# flight_unit.net
KiCad netlist of a schematic drawn in EAGLE
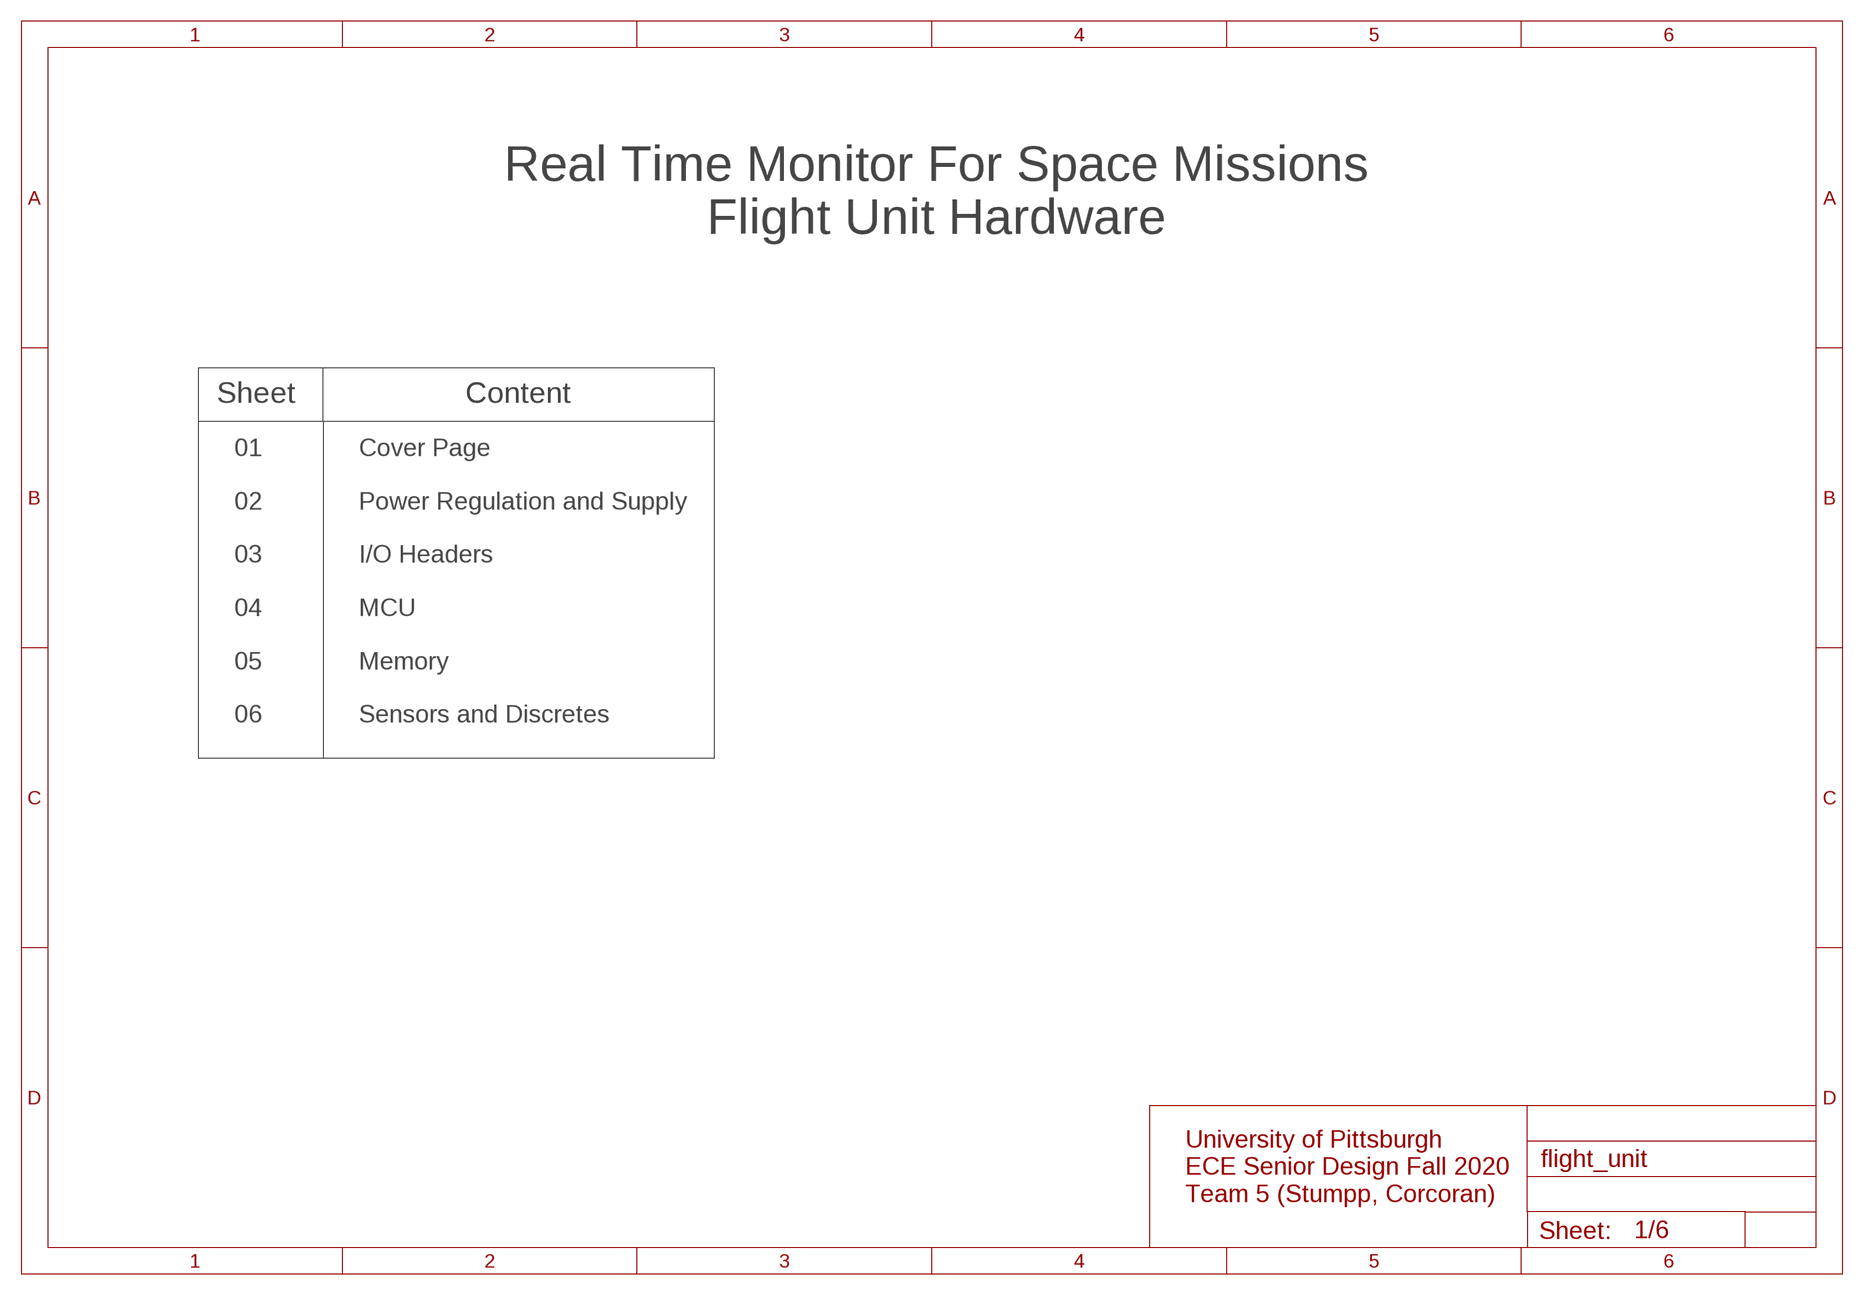
[diagram p0: schematic, sheet 1]
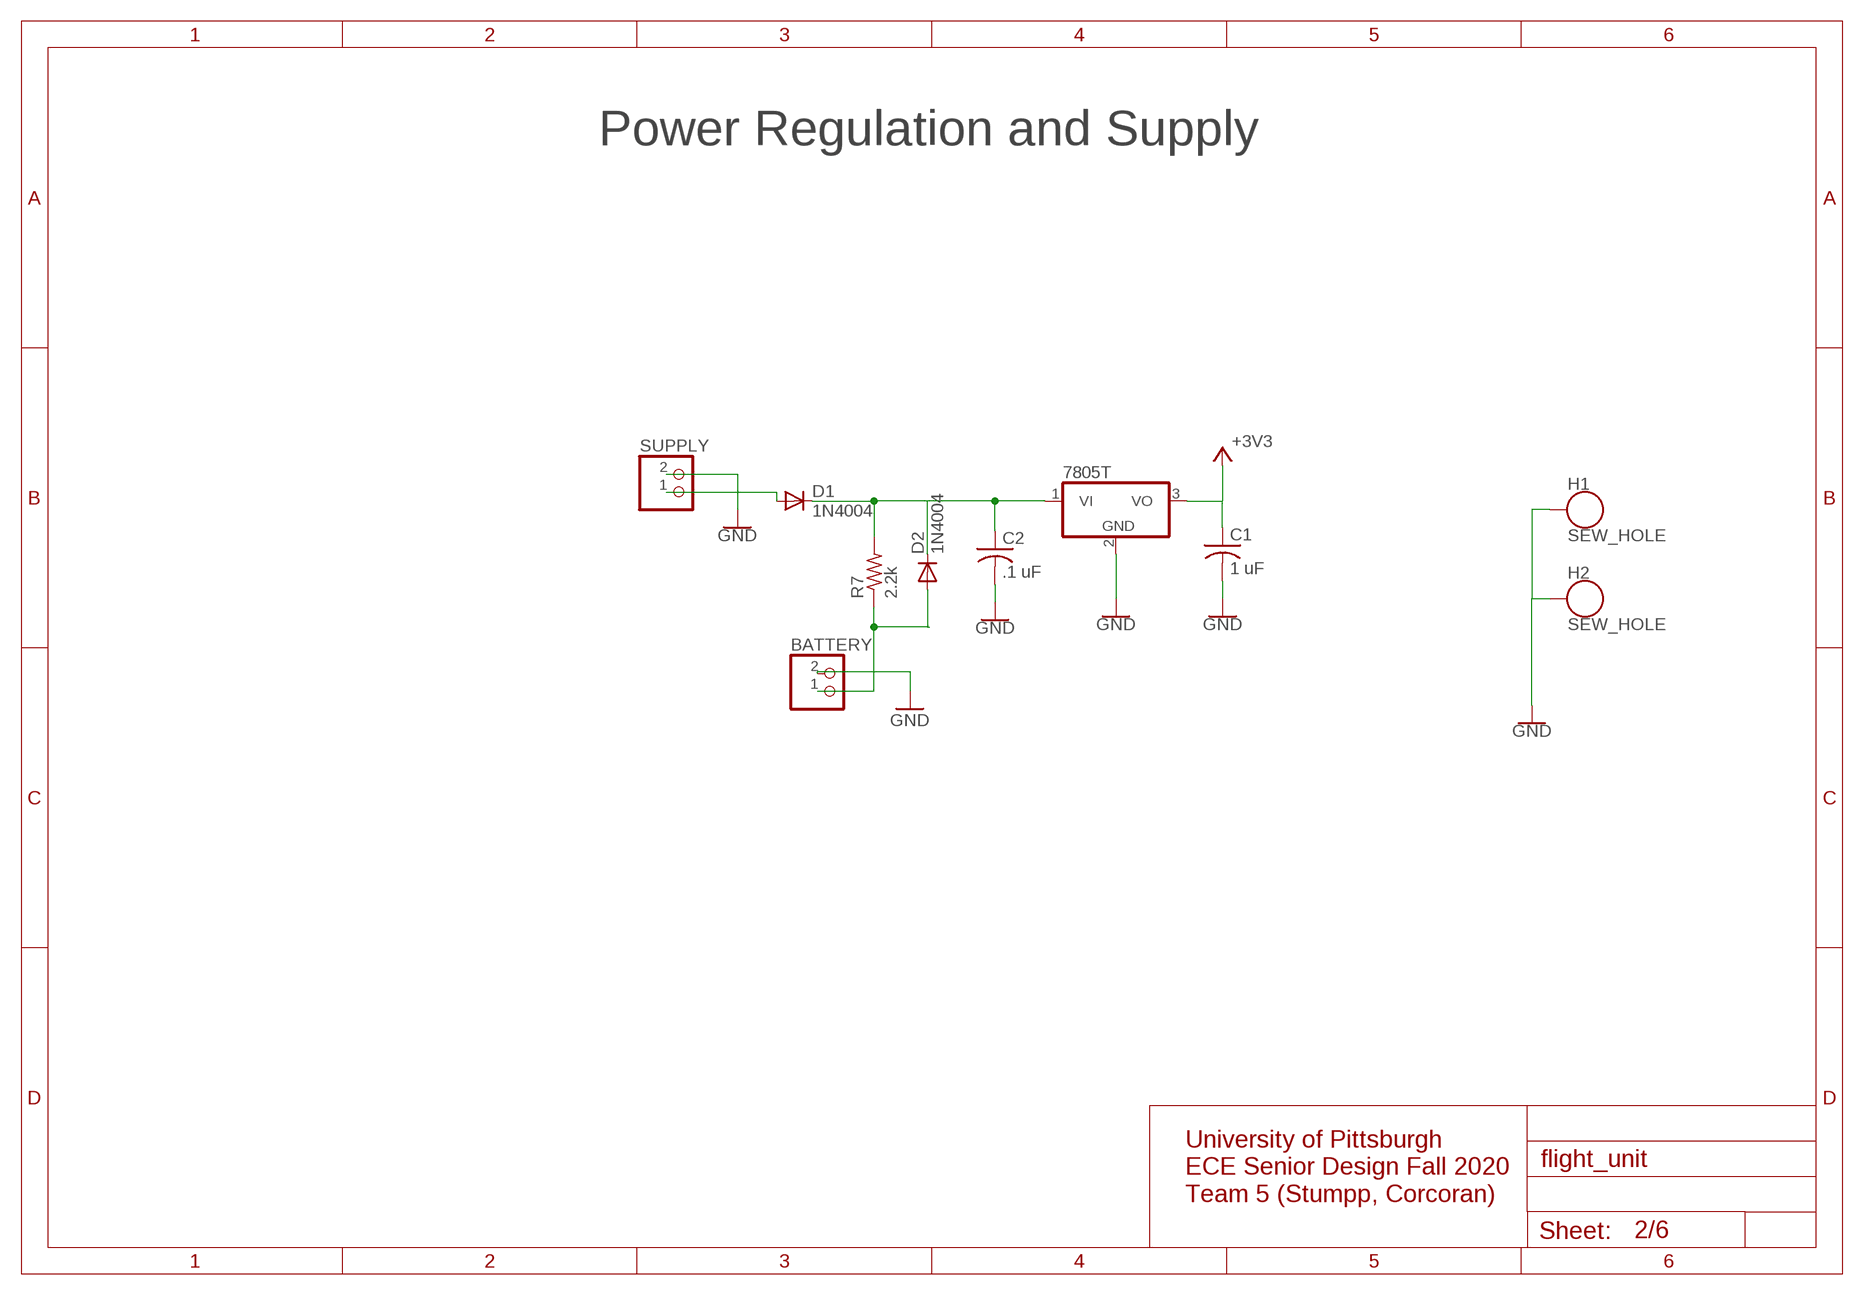
[diagram p1: schematic, sheet 2]
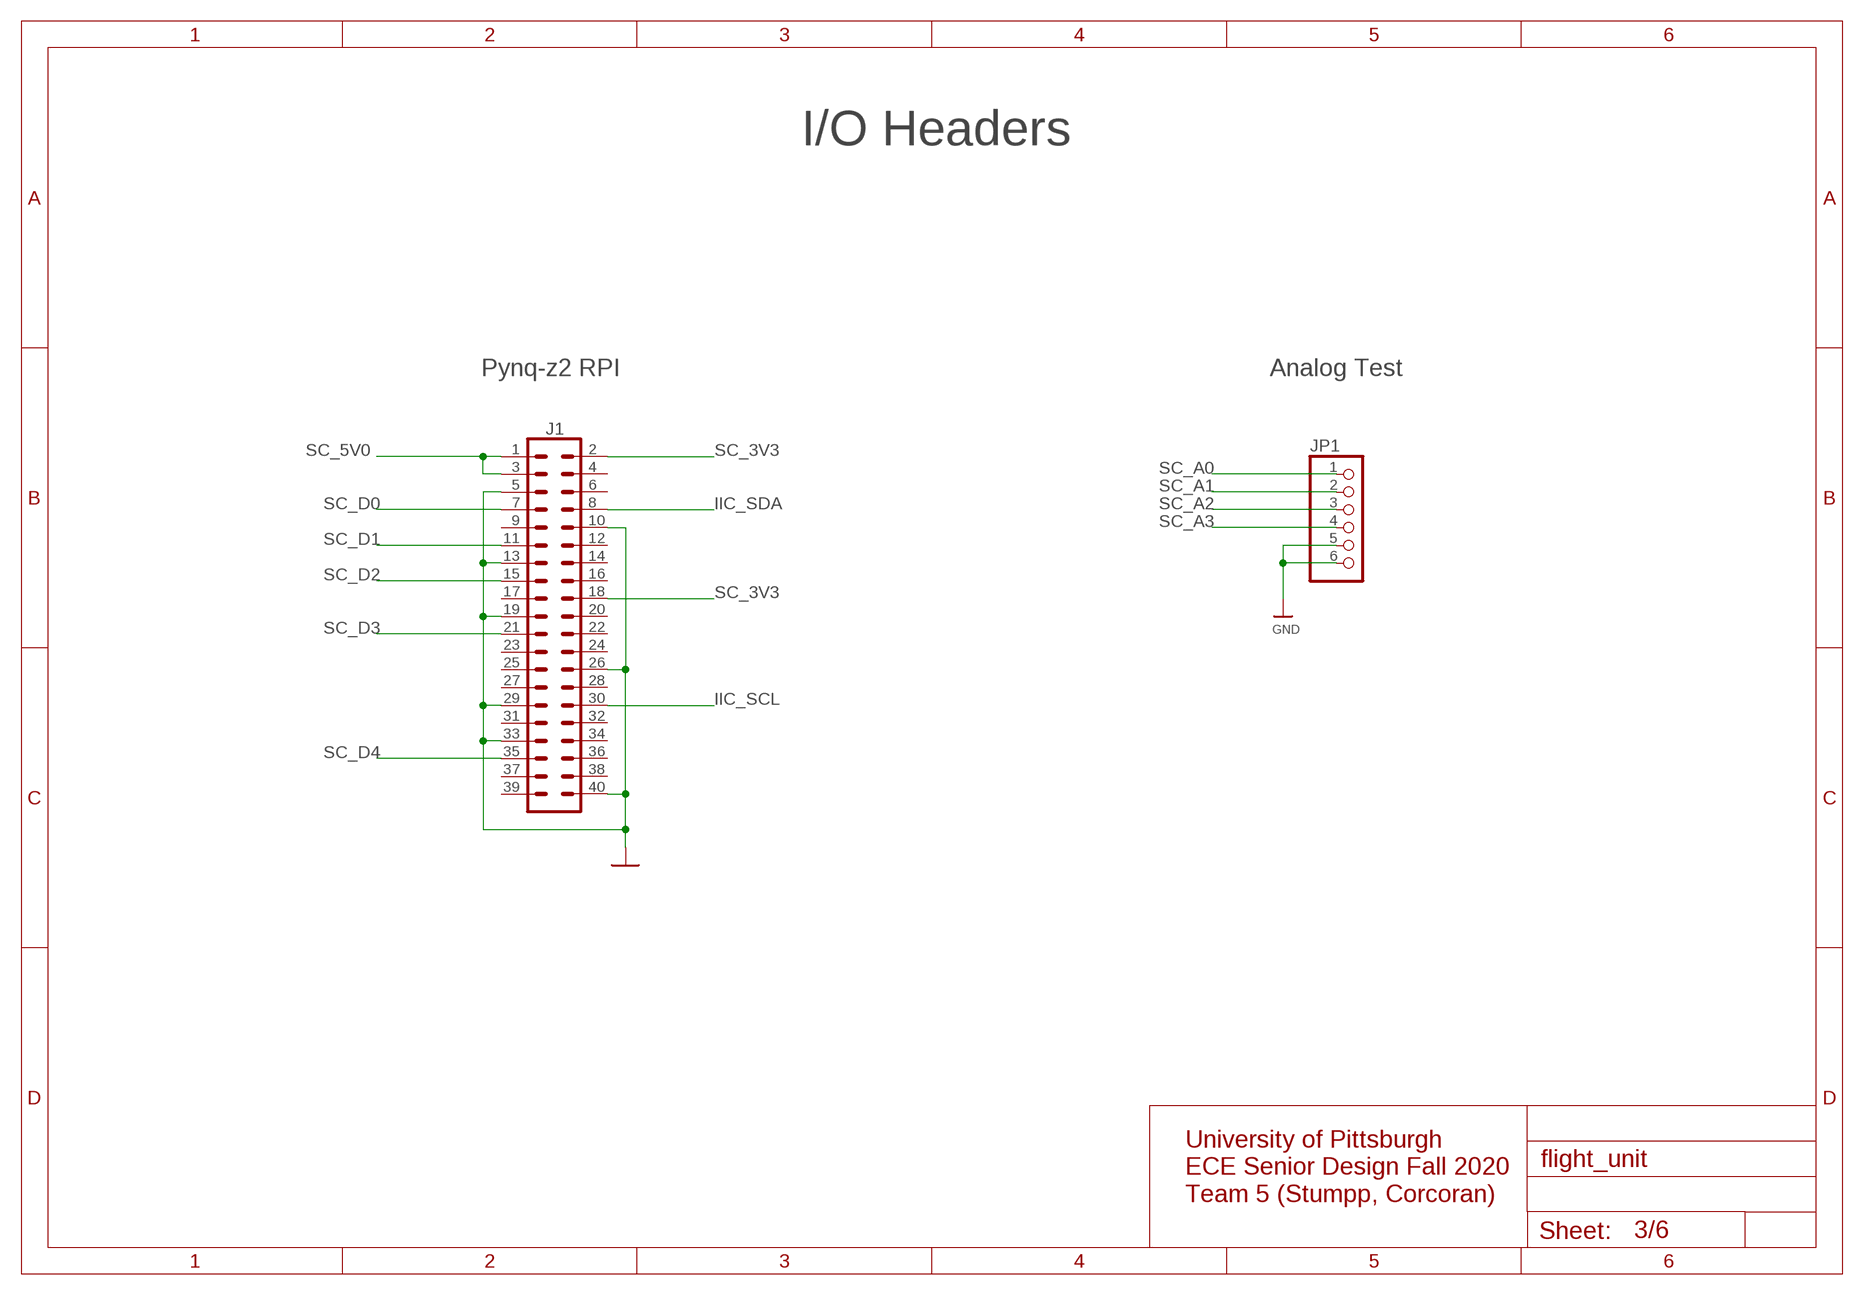
[diagram p2: schematic, sheet 3]
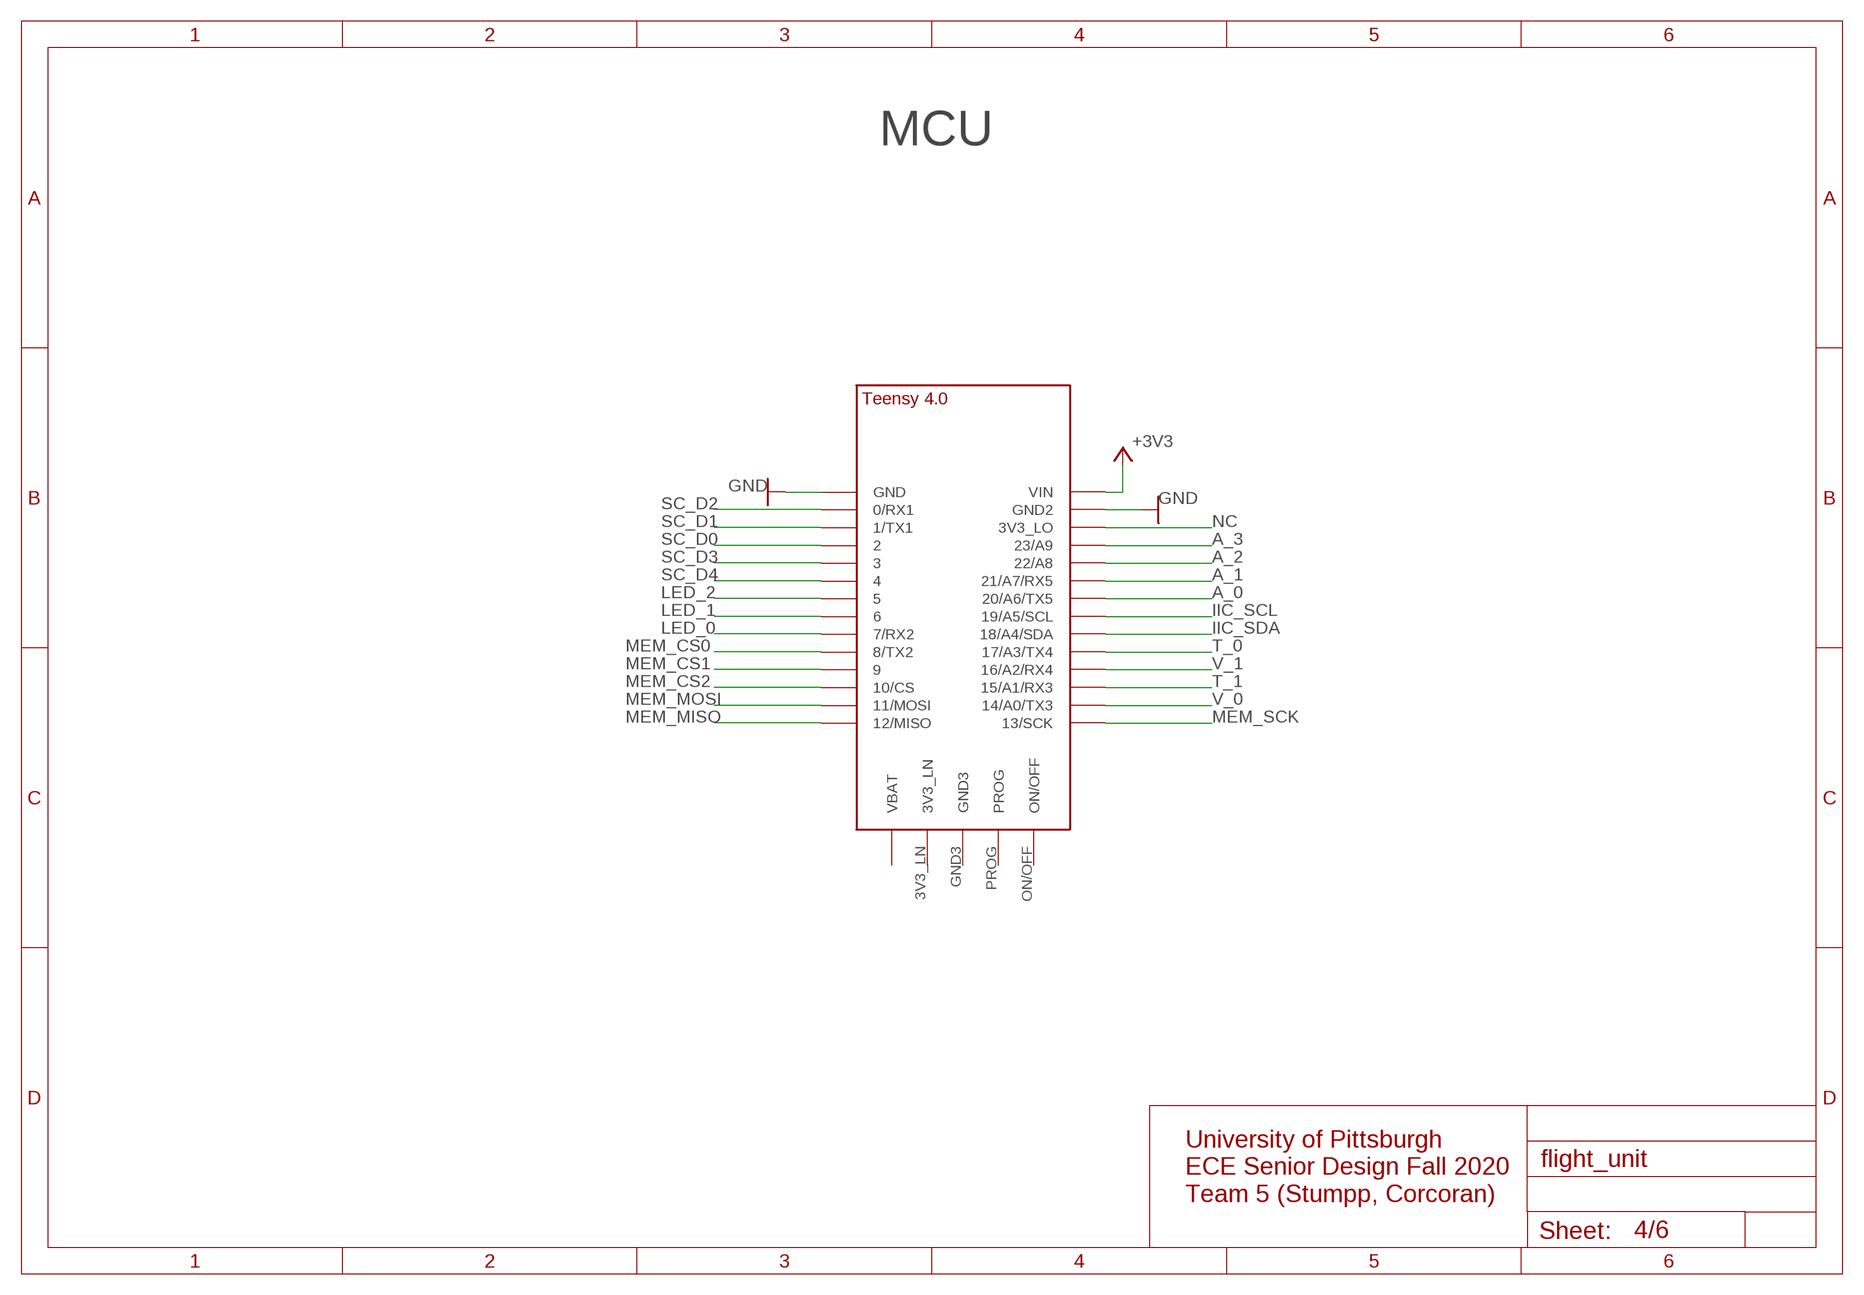
[diagram p3: schematic, sheet 4]
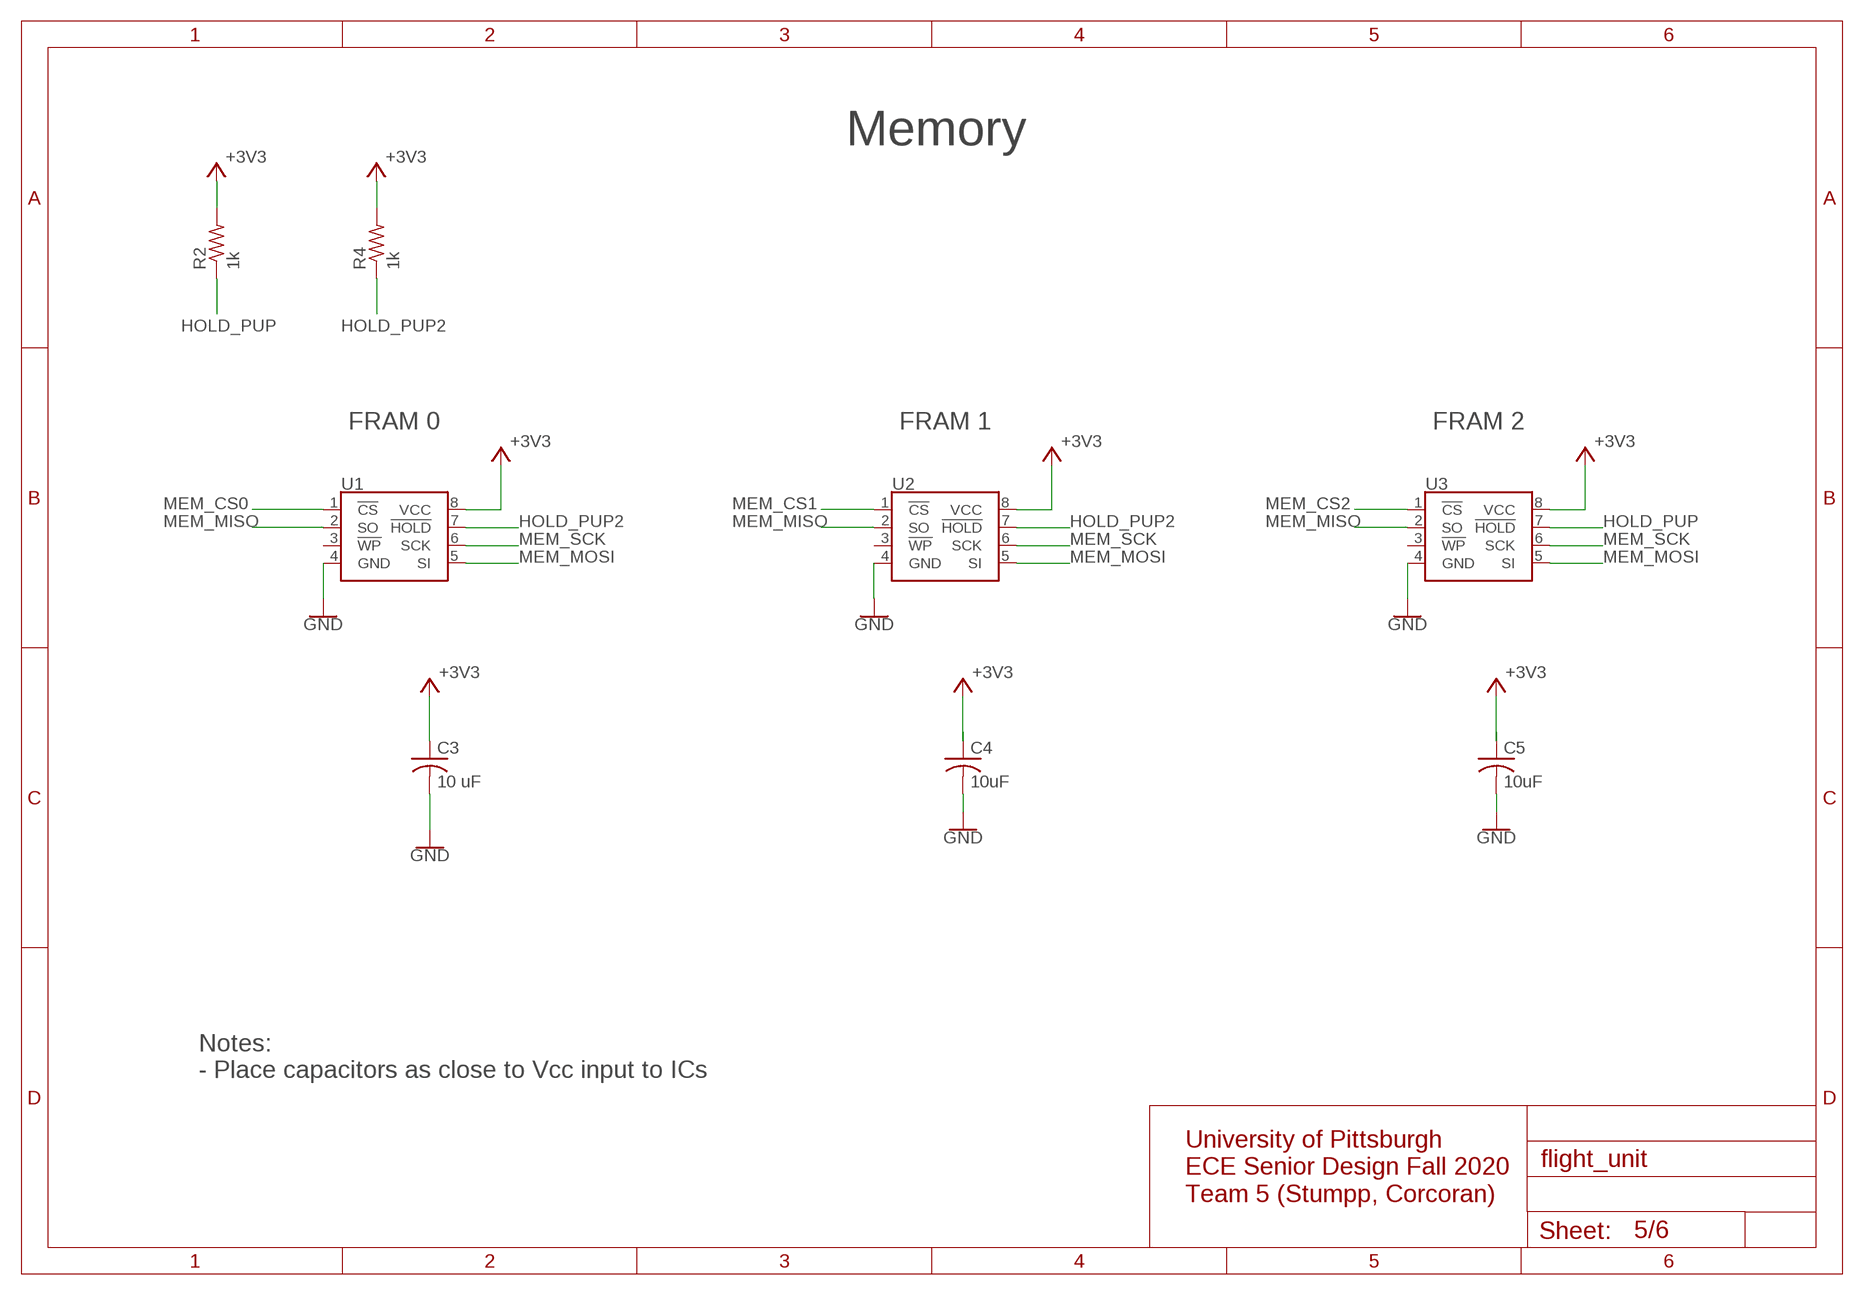
[diagram p4: schematic, sheet 5]
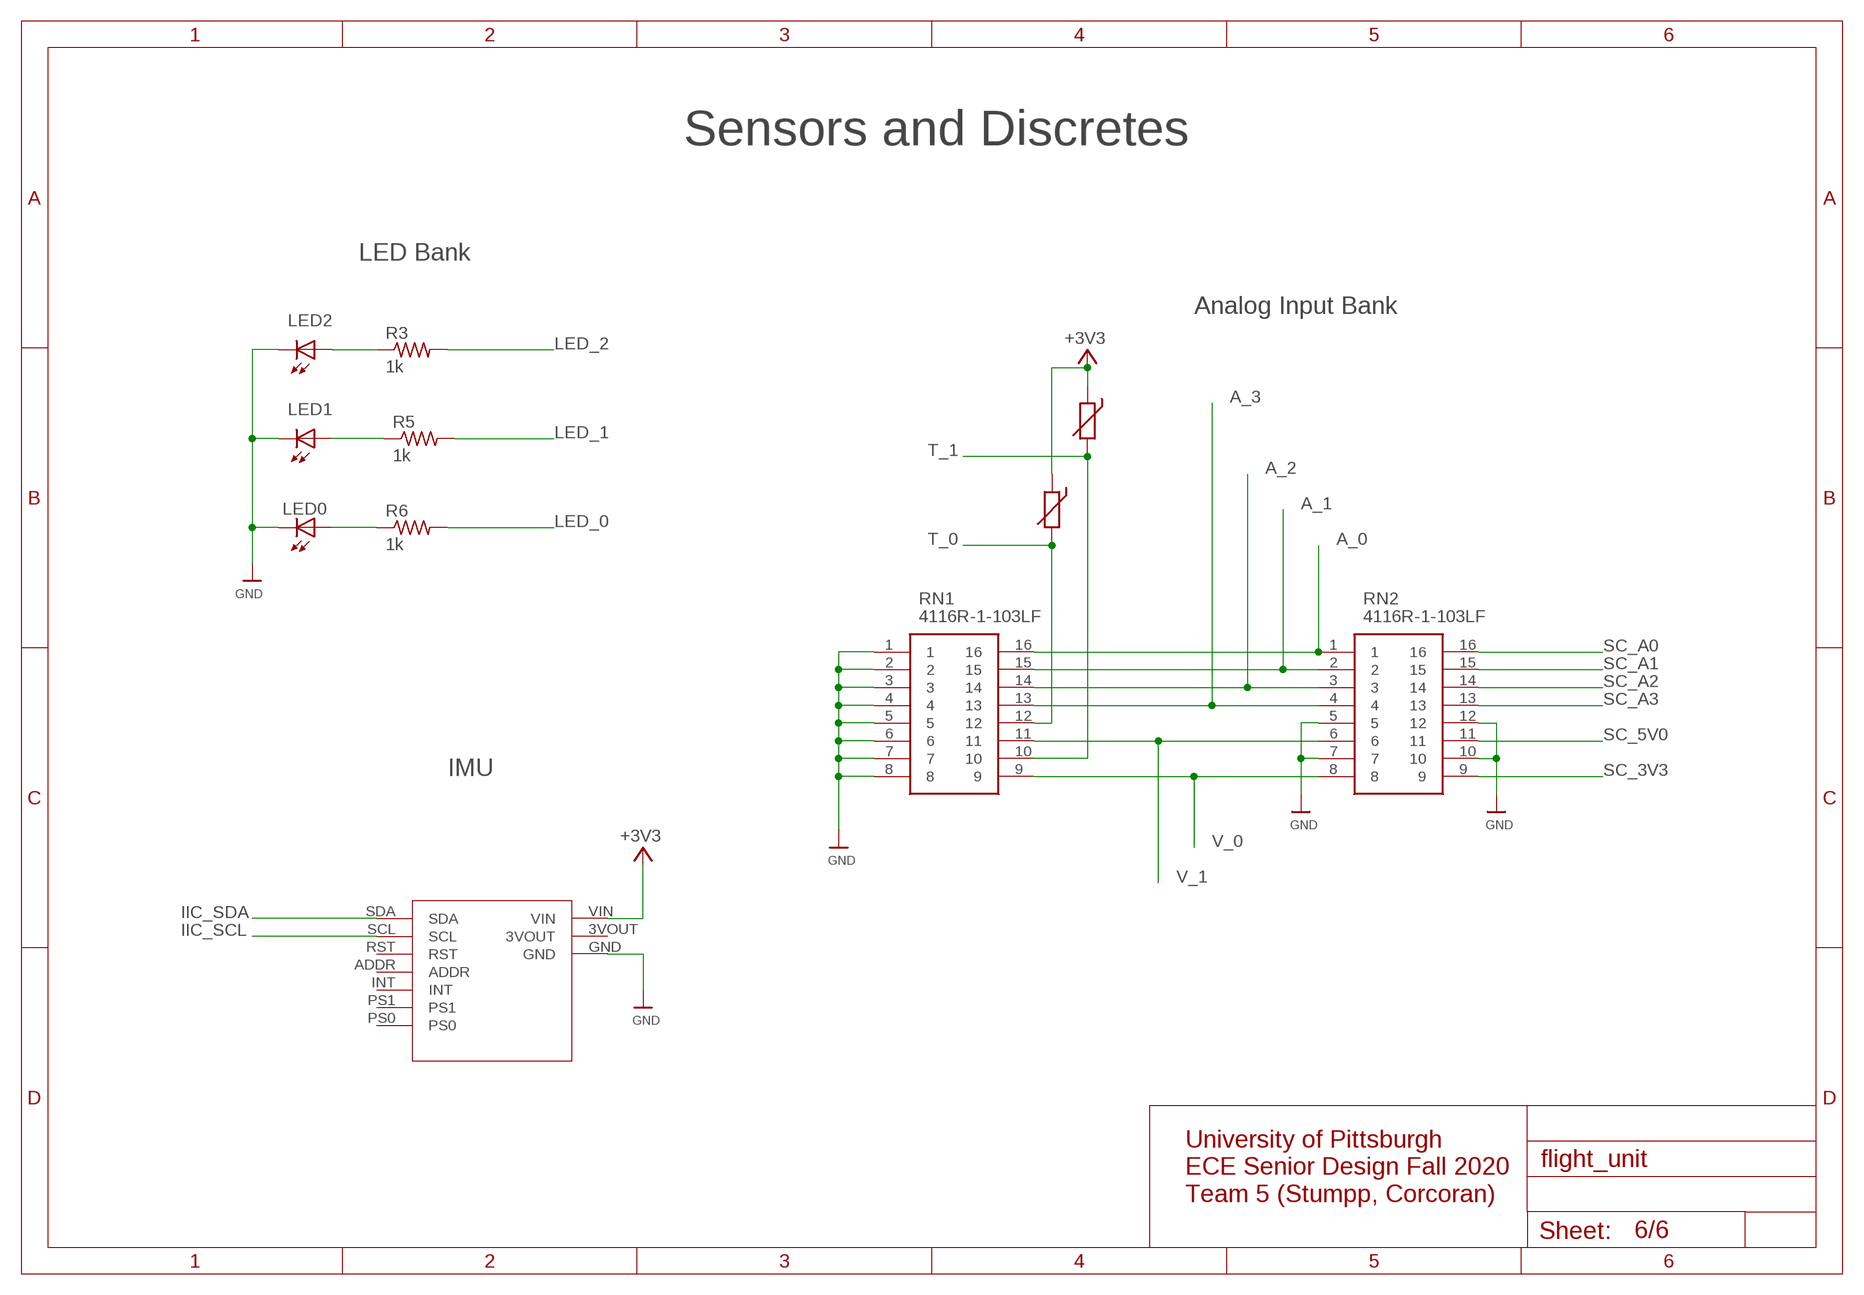
[diagram p5: schematic, sheet 6]

(export (version "E")
  (design (tool "Eeschema 10.0.6"))
  (components
    (comp (ref "BATTERY")
      (value "JST_2PIN-THM")
      (footprint "eagle-import:JST-PH-2-THM")
      (libsource (lib "eagle-import") (part "JST_2PIN-THM"))
    )
    (comp (ref "C1")
      (value "1 uF")
      (footprint "eagle-import:C0805K")
      (libsource (lib "eagle-import") (part "C-USC0805K"))
    )
    (comp (ref "C2")
      (value ".1 uF")
      (footprint "eagle-import:C0805K")
      (libsource (lib "eagle-import") (part "C-USC0805K"))
    )
    (comp (ref "D1")
      (value "1N4004")
      (footprint "eagle-import:DO41-10")
      (libsource (lib "eagle-import") (part "1N4004"))
    )
    (comp (ref "D2")
      (value "1N4004")
      (footprint "eagle-import:DO41-10")
      (libsource (lib "eagle-import") (part "1N4004"))
    )
    (comp (ref "H1")
      (value "SEW_HOLE")
      (footprint "eagle-import:SIMPLE_HOLE")
      (libsource (lib "eagle-import") (part "SEW_HOLE"))
    )
    (comp (ref "H2")
      (value "SEW_HOLE")
      (footprint "eagle-import:SIMPLE_HOLE")
      (libsource (lib "eagle-import") (part "SEW_HOLE"))
    )
    (comp (ref "IC2")
      (value "7805T")
      (footprint "eagle-import:TO220H")
      (libsource (lib "eagle-import") (part "78T05"))
    )
    (comp (ref "R7")
      (value "2.2k")
      (footprint "eagle-import:R0805")
      (libsource (lib "eagle-import") (part "R-US_R0805"))
    )
    (comp (ref "SUPPLY")
      (value "JST_2PIN-THM")
      (footprint "eagle-import:JST-PH-2-THM")
      (libsource (lib "eagle-import") (part "JST_2PIN-THM"))
    )
    (comp (ref "U$1")
      (value "TEENSY_4.0")
      (footprint "eagle-import:TEENSY_4.0")
      (libsource (lib "eagle-import") (part "TEENSY_4.0"))
    )
    (comp (ref "LED0")
      (value "LED3MM")
      (footprint "eagle-import:LED3MM")
      (libsource (lib "eagle-import") (part "LED3MM"))
    )
    (comp (ref "LED1")
      (value "LED3MM")
      (footprint "eagle-import:LED3MM")
      (libsource (lib "eagle-import") (part "LED3MM"))
    )
    (comp (ref "LED2")
      (value "LED3MM")
      (footprint "eagle-import:LED3MM")
      (libsource (lib "eagle-import") (part "LED3MM"))
    )
    (comp (ref "R3")
      (value "1k")
      (footprint "eagle-import:R0805")
      (libsource (lib "eagle-import") (part "R-US_R0805"))
    )
    (comp (ref "R5")
      (value "1k")
      (footprint "eagle-import:R0805")
      (libsource (lib "eagle-import") (part "R-US_R0805"))
    )
    (comp (ref "R6")
      (value "1k")
      (footprint "eagle-import:R0805")
      (libsource (lib "eagle-import") (part "R-US_R0805"))
    )
    (comp (ref "R8")
      (value "THERMISTOR-2,5")
      (footprint "eagle-import:RS-2,5")
      (fields (field (name "SPICEPREFIX") "R"))
      (libsource (lib "eagle-import") (part "THERMISTOR-2,5"))
    )
    (comp (ref "RN1")
      (value "4116R-1-103LF")
      (footprint "eagle-import:DIP787W49P254L2197H469Q16N")
      (fields (field (name "MOUSER_PART_NUMBER") "652-4116R-1LF-10K"))
      (libsource (lib "eagle-import") (part "4116R-1-103LF"))
    )
    (comp (ref "RN2")
      (value "4116R-1-103LF")
      (footprint "eagle-import:DIP787W49P254L2197H469Q16N")
      (fields (field (name "MOUSER_PART_NUMBER") "652-4116R-1LF-10K"))
      (libsource (lib "eagle-import") (part "4116R-1-103LF"))
    )
    (comp (ref "T1")
      (value "THERMISTOR-2,5")
      (footprint "eagle-import:RS-2,5")
      (libsource (lib "eagle-import") (part "THERMISTOR-2,5"))
    )
    (comp (ref "U$3")
      (value "IMU_BREAKOUT")
      (footprint "eagle-import:BNO055_BREAKOUT")
      (libsource (lib "eagle-import") (part "IMU_BREAKOUT"))
    )
    (comp (ref "C3")
      (value "10 uF")
      (footprint "eagle-import:C0805K")
      (libsource (lib "eagle-import") (part "C-USC0805K"))
    )
    (comp (ref "C4")
      (value "10uF")
      (footprint "eagle-import:C0805K")
      (libsource (lib "eagle-import") (part "C-USC0805K"))
    )
    (comp (ref "C5")
      (value "10uF")
      (footprint "eagle-import:C0805K")
      (libsource (lib "eagle-import") (part "C-USC0805K"))
    )
    (comp (ref "R2")
      (value "1k")
      (footprint "eagle-import:R0805")
      (libsource (lib "eagle-import") (part "R-US_R0805"))
    )
    (comp (ref "R4")
      (value "1k")
      (footprint "eagle-import:R0805")
      (libsource (lib "eagle-import") (part "R-US_R0805"))
    )
    (comp (ref "U1")
      (value "4MB Flash")
      (footprint "eagle-import:SO08")
      (libsource (lib "eagle-import") (part "AT25SF041"))
    )
    (comp (ref "U2")
      (value "4MB Flash")
      (footprint "eagle-import:SO08")
      (libsource (lib "eagle-import") (part "AT25SF041"))
    )
    (comp (ref "U3")
      (value "4MB Flash")
      (footprint "eagle-import:SO08")
      (libsource (lib "eagle-import") (part "AT25SF041"))
    )
    (comp (ref "J1")
      (value "CONN_20X2SHROUDED")
      (footprint "eagle-import:2X20_SHROUDED")
      (libsource (lib "eagle-import") (part "CONN_20X2SHROUDED"))
    )
    (comp (ref "JP1")
      (value "PINHD-1X6B")
      (footprint "eagle-import:1X06-BIG")
      (libsource (lib "eagle-import") (part "PINHD-1X6B"))
    )
  )
  (nets
    (net (code "1") (name "+3V3") (class "Default")
      (node (ref "C1") (pin "1") (pinfunction "1_1") (pintype "passive"))
      (node (ref "C3") (pin "1") (pinfunction "1_1") (pintype "passive"))
      (node (ref "C4") (pin "1") (pinfunction "1_1") (pintype "passive"))
      (node (ref "C5") (pin "1") (pinfunction "1_1") (pintype "passive"))
      (node (ref "IC2") (pin "3") (pinfunction "VO_3") (pintype "passive"))
      (node (ref "R2") (pin "2") (pinfunction "2_2") (pintype "passive"))
      (node (ref "R4") (pin "2") (pinfunction "2_2") (pintype "passive"))
      (node (ref "R8") (pin "1") (pinfunction "1_1") (pintype "passive"))
      (node (ref "T1") (pin "1") (pinfunction "1_1") (pintype "passive"))
      (node (ref "U$1") (pin "VIN") (pinfunction "VIN_VIN") (pintype "bidirectional"))
      (node (ref "U$3") (pin "VIN") (pinfunction "VIN_VIN") (pintype "bidirectional"))
      (node (ref "U1") (pin "8") (pinfunction "VCC_8") (pintype "bidirectional"))
      (node (ref "U2") (pin "8") (pinfunction "VCC_8") (pintype "bidirectional"))
      (node (ref "U3") (pin "8") (pinfunction "VCC_8") (pintype "bidirectional"))
    )
    (net (code "2") (name "A_0") (class "Default")
      (node (ref "RN1") (pin "16") (pinfunction "16_16") (pintype "bidirectional"))
      (node (ref "RN2") (pin "1") (pinfunction "1_1") (pintype "bidirectional"))
      (node (ref "U$1") (pin "20/A6") (pinfunction "20/A6/TX5_20/A6") (pintype "bidirectional"))
    )
    (net (code "3") (name "A_1") (class "Default")
      (node (ref "RN1") (pin "15") (pinfunction "15_15") (pintype "bidirectional"))
      (node (ref "RN2") (pin "2") (pinfunction "2_2") (pintype "bidirectional"))
      (node (ref "U$1") (pin "21/A7") (pinfunction "21/A7/RX5_21/A7") (pintype "bidirectional"))
    )
    (net (code "4") (name "A_2") (class "Default")
      (node (ref "RN1") (pin "14") (pinfunction "14_14") (pintype "bidirectional"))
      (node (ref "RN2") (pin "3") (pinfunction "3_3") (pintype "bidirectional"))
      (node (ref "U$1") (pin "22/A8") (pinfunction "22/A8_22/A8") (pintype "bidirectional"))
    )
    (net (code "5") (name "A_3") (class "Default")
      (node (ref "RN1") (pin "13") (pinfunction "13_13") (pintype "bidirectional"))
      (node (ref "RN2") (pin "4") (pinfunction "4_4") (pintype "bidirectional"))
      (node (ref "U$1") (pin "23/A9") (pinfunction "23/A9_23/A9") (pintype "bidirectional"))
    )
    (net (code "6") (name "GND") (class "Default")
      (node (ref "BATTERY") (pin "2") (pinfunction "1_2") (pintype "passive"))
      (node (ref "C1") (pin "2") (pinfunction "2_2") (pintype "passive"))
      (node (ref "C2") (pin "2") (pinfunction "2_2") (pintype "passive"))
      (node (ref "C3") (pin "2") (pinfunction "2_2") (pintype "passive"))
      (node (ref "C4") (pin "2") (pinfunction "2_2") (pintype "passive"))
      (node (ref "C5") (pin "2") (pinfunction "2_2") (pintype "passive"))
      (node (ref "H1") (pin "P$1") (pinfunction "P$1_P$1") (pintype "bidirectional"))
      (node (ref "H2") (pin "P$1") (pinfunction "P$1_P$1") (pintype "bidirectional"))
      (node (ref "IC2") (pin "2") (pinfunction "GND_2") (pintype "passive"))
      (node (ref "J1") (pin "10") (pinfunction "10_10") (pintype "passive"))
      (node (ref "J1") (pin "13") (pinfunction "13_13") (pintype "passive"))
      (node (ref "J1") (pin "19") (pinfunction "19_19") (pintype "passive"))
      (node (ref "J1") (pin "26") (pinfunction "26_26") (pintype "passive"))
      (node (ref "J1") (pin "29") (pinfunction "29_29") (pintype "passive"))
      (node (ref "J1") (pin "33") (pinfunction "33_33") (pintype "passive"))
      (node (ref "J1") (pin "40") (pinfunction "40_40") (pintype "passive"))
      (node (ref "J1") (pin "5") (pinfunction "5_5") (pintype "passive"))
      (node (ref "JP1") (pin "5") (pinfunction "5_5") (pintype "passive"))
      (node (ref "JP1") (pin "6") (pinfunction "6_6") (pintype "passive"))
      (node (ref "LED0") (pin "K") (pinfunction "C_K") (pintype "passive"))
      (node (ref "LED1") (pin "K") (pinfunction "C_K") (pintype "passive"))
      (node (ref "LED2") (pin "K") (pinfunction "C_K") (pintype "passive"))
      (node (ref "RN1") (pin "1") (pinfunction "1_1") (pintype "bidirectional"))
      (node (ref "RN1") (pin "2") (pinfunction "2_2") (pintype "bidirectional"))
      (node (ref "RN1") (pin "3") (pinfunction "3_3") (pintype "bidirectional"))
      (node (ref "RN1") (pin "4") (pinfunction "4_4") (pintype "bidirectional"))
      (node (ref "RN1") (pin "5") (pinfunction "5_5") (pintype "bidirectional"))
      (node (ref "RN1") (pin "6") (pinfunction "6_6") (pintype "bidirectional"))
      (node (ref "RN1") (pin "7") (pinfunction "7_7") (pintype "bidirectional"))
      (node (ref "RN1") (pin "8") (pinfunction "8_8") (pintype "bidirectional"))
      (node (ref "RN2") (pin "10") (pinfunction "10_10") (pintype "bidirectional"))
      (node (ref "RN2") (pin "12") (pinfunction "12_12") (pintype "bidirectional"))
      (node (ref "RN2") (pin "5") (pinfunction "5_5") (pintype "bidirectional"))
      (node (ref "RN2") (pin "7") (pinfunction "7_7") (pintype "bidirectional"))
      (node (ref "SUPPLY") (pin "2") (pinfunction "1_2") (pintype "passive"))
      (node (ref "U$1") (pin "GND") (pinfunction "GND_GND") (pintype "bidirectional"))
      (node (ref "U$1") (pin "GND2") (pinfunction "GND2_GND2") (pintype "bidirectional"))
      (node (ref "U$3") (pin "GND") (pinfunction "GND_GND") (pintype "bidirectional"))
      (node (ref "U1") (pin "4") (pinfunction "GND_4") (pintype "bidirectional"))
      (node (ref "U2") (pin "4") (pinfunction "GND_4") (pintype "bidirectional"))
      (node (ref "U3") (pin "4") (pinfunction "GND_4") (pintype "bidirectional"))
    )
    (net (code "7") (name "HOLD_PUP") (class "Default")
      (node (ref "R2") (pin "1") (pinfunction "1_1") (pintype "passive"))
      (node (ref "U3") (pin "7") (pinfunction "~{HOLD}_7") (pintype "bidirectional"))
    )
    (net (code "8") (name "HOLD_PUP2") (class "Default")
      (node (ref "R4") (pin "1") (pinfunction "1_1") (pintype "passive"))
      (node (ref "U1") (pin "7") (pinfunction "~{HOLD}_7") (pintype "bidirectional"))
      (node (ref "U2") (pin "7") (pinfunction "~{HOLD}_7") (pintype "bidirectional"))
    )
    (net (code "9") (name "IIC_SCL") (class "Default")
      (node (ref "J1") (pin "30") (pinfunction "30_30") (pintype "passive"))
      (node (ref "U$1") (pin "19/A5/SCL") (pinfunction "19/A5/SCL_19/A5/SCL") (pintype "bidirectional"))
      (node (ref "U$3") (pin "SCL") (pinfunction "SCL_SCL") (pintype "bidirectional"))
    )
    (net (code "10") (name "IIC_SDA") (class "Default")
      (node (ref "J1") (pin "8") (pinfunction "8_8") (pintype "passive"))
      (node (ref "U$1") (pin "18/A4/SDA") (pinfunction "18/A4/SDA_18/A4/SDA") (pintype "bidirectional"))
      (node (ref "U$3") (pin "SDA") (pinfunction "SDA_SDA") (pintype "bidirectional"))
    )
    (net (code "11") (name "LED_0") (class "Default")
      (node (ref "R6") (pin "2") (pinfunction "2_2") (pintype "passive"))
      (node (ref "U$1") (pin "7") (pinfunction "7/RX2_7") (pintype "bidirectional"))
    )
    (net (code "12") (name "LED_1") (class "Default")
      (node (ref "R5") (pin "2") (pinfunction "2_2") (pintype "passive"))
      (node (ref "U$1") (pin "6") (pinfunction "6_6") (pintype "bidirectional"))
    )
    (net (code "13") (name "LED_2") (class "Default")
      (node (ref "R3") (pin "2") (pinfunction "2_2") (pintype "passive"))
      (node (ref "U$1") (pin "5") (pinfunction "5_5") (pintype "bidirectional"))
    )
    (net (code "14") (name "MEM_CS0") (class "Default")
      (node (ref "U$1") (pin "8") (pinfunction "8/TX2_8") (pintype "bidirectional"))
      (node (ref "U1") (pin "1") (pinfunction "~{CS}_1") (pintype "bidirectional"))
    )
    (net (code "15") (name "MEM_CS1") (class "Default")
      (node (ref "U$1") (pin "9/CS") (pinfunction "9_9/CS") (pintype "bidirectional"))
      (node (ref "U2") (pin "1") (pinfunction "~{CS}_1") (pintype "bidirectional"))
    )
    (net (code "16") (name "MEM_CS2") (class "Default")
      (node (ref "U$1") (pin "10/CS") (pinfunction "10/CS_10/CS") (pintype "bidirectional"))
      (node (ref "U3") (pin "1") (pinfunction "~{CS}_1") (pintype "bidirectional"))
    )
    (net (code "17") (name "MEM_MISO") (class "Default")
      (node (ref "U$1") (pin "12/MISO") (pinfunction "12/MISO_12/MISO") (pintype "bidirectional"))
      (node (ref "U1") (pin "2") (pinfunction "SO_2") (pintype "bidirectional"))
      (node (ref "U2") (pin "2") (pinfunction "SO_2") (pintype "bidirectional"))
      (node (ref "U3") (pin "2") (pinfunction "SO_2") (pintype "bidirectional"))
    )
    (net (code "18") (name "MEM_MOSI") (class "Default")
      (node (ref "U$1") (pin "11/MOSI") (pinfunction "11/MOSI_11/MOSI") (pintype "bidirectional"))
      (node (ref "U1") (pin "5") (pinfunction "SI_5") (pintype "bidirectional"))
      (node (ref "U2") (pin "5") (pinfunction "SI_5") (pintype "bidirectional"))
      (node (ref "U3") (pin "5") (pinfunction "SI_5") (pintype "bidirectional"))
    )
    (net (code "19") (name "MEM_SCK") (class "Default")
      (node (ref "U$1") (pin "13/SCK") (pinfunction "13/SCK_13/SCK") (pintype "bidirectional"))
      (node (ref "U1") (pin "6") (pinfunction "SCK_6") (pintype "bidirectional"))
      (node (ref "U2") (pin "6") (pinfunction "SCK_6") (pintype "bidirectional"))
      (node (ref "U3") (pin "6") (pinfunction "SCK_6") (pintype "bidirectional"))
    )
    (net (code "20") (name "NC") (class "Default")
      (node (ref "U$1") (pin "3V3_LO") (pinfunction "3V3_LO_3V3_LO") (pintype "bidirectional"))
    )
    (net (code "21") (name "Net-(BATTERY-2)") (class "Default")
      (node (ref "BATTERY") (pin "1") (pinfunction "2_1") (pintype "passive"))
      (node (ref "D2") (pin "A") (pinfunction "A_A") (pintype "passive"))
      (node (ref "R7") (pin "1") (pinfunction "1_1") (pintype "passive"))
    )
    (net (code "22") (name "Net-(IC2-VI)") (class "Default")
      (node (ref "C2") (pin "1") (pinfunction "1_1") (pintype "passive"))
      (node (ref "D1") (pin "C") (pinfunction "C_C") (pintype "passive"))
      (node (ref "D2") (pin "C") (pinfunction "C_C") (pintype "passive"))
      (node (ref "IC2") (pin "1") (pinfunction "VI_1") (pintype "input"))
      (node (ref "R7") (pin "2") (pinfunction "2_2") (pintype "passive"))
    )
    (net (code "23") (name "Net-(LED0-PadA)") (class "Default")
      (node (ref "LED0") (pin "A") (pinfunction "A_A") (pintype "passive"))
      (node (ref "R6") (pin "1") (pinfunction "1_1") (pintype "passive"))
    )
    (net (code "24") (name "Net-(LED1-PadA)") (class "Default")
      (node (ref "LED1") (pin "A") (pinfunction "A_A") (pintype "passive"))
      (node (ref "R5") (pin "1") (pinfunction "1_1") (pintype "passive"))
    )
    (net (code "25") (name "Net-(LED2-PadA)") (class "Default")
      (node (ref "LED2") (pin "A") (pinfunction "A_A") (pintype "passive"))
      (node (ref "R3") (pin "1") (pinfunction "1_1") (pintype "passive"))
    )
    (net (code "26") (name "Net-(SUPPLY-2)") (class "Default")
      (node (ref "D1") (pin "A") (pinfunction "A_A") (pintype "passive"))
      (node (ref "SUPPLY") (pin "1") (pinfunction "2_1") (pintype "passive"))
    )
    (net (code "27") (name "SC_3V3") (class "Default")
      (node (ref "J1") (pin "18") (pinfunction "18_18") (pintype "passive"))
      (node (ref "J1") (pin "2") (pinfunction "2_2") (pintype "passive"))
      (node (ref "RN2") (pin "9") (pinfunction "9_9") (pintype "bidirectional"))
    )
    (net (code "28") (name "SC_5V0") (class "Default")
      (node (ref "J1") (pin "1") (pinfunction "1_1") (pintype "passive"))
      (node (ref "J1") (pin "3") (pinfunction "3_3") (pintype "passive"))
      (node (ref "RN2") (pin "11") (pinfunction "11_11") (pintype "bidirectional"))
    )
    (net (code "29") (name "SC_A0") (class "Default")
      (node (ref "JP1") (pin "1") (pinfunction "1_1") (pintype "passive"))
      (node (ref "RN2") (pin "16") (pinfunction "16_16") (pintype "bidirectional"))
    )
    (net (code "30") (name "SC_A1") (class "Default")
      (node (ref "JP1") (pin "2") (pinfunction "2_2") (pintype "passive"))
      (node (ref "RN2") (pin "15") (pinfunction "15_15") (pintype "bidirectional"))
    )
    (net (code "31") (name "SC_A2") (class "Default")
      (node (ref "JP1") (pin "3") (pinfunction "3_3") (pintype "passive"))
      (node (ref "RN2") (pin "14") (pinfunction "14_14") (pintype "bidirectional"))
    )
    (net (code "32") (name "SC_A3") (class "Default")
      (node (ref "JP1") (pin "4") (pinfunction "4_4") (pintype "passive"))
      (node (ref "RN2") (pin "13") (pinfunction "13_13") (pintype "bidirectional"))
    )
    (net (code "33") (name "SC_D0") (class "Default")
      (node (ref "J1") (pin "7") (pinfunction "7_7") (pintype "passive"))
      (node (ref "U$1") (pin "2") (pinfunction "2_2") (pintype "bidirectional"))
    )
    (net (code "34") (name "SC_D1") (class "Default")
      (node (ref "J1") (pin "11") (pinfunction "11_11") (pintype "passive"))
      (node (ref "U$1") (pin "1/TX") (pinfunction "1/TX1_1/TX") (pintype "bidirectional"))
    )
    (net (code "35") (name "SC_D2") (class "Default")
      (node (ref "J1") (pin "15") (pinfunction "15_15") (pintype "passive"))
      (node (ref "U$1") (pin "0/RX") (pinfunction "0/RX1_0/RX") (pintype "bidirectional"))
    )
    (net (code "36") (name "SC_D3") (class "Default")
      (node (ref "J1") (pin "21") (pinfunction "21_21") (pintype "passive"))
      (node (ref "U$1") (pin "3/CANTX") (pinfunction "3_3/CANTX") (pintype "bidirectional"))
    )
    (net (code "37") (name "SC_D4") (class "Default")
      (node (ref "J1") (pin "35") (pinfunction "35_35") (pintype "passive"))
      (node (ref "U$1") (pin "4/CANRX") (pinfunction "4_4/CANRX") (pintype "bidirectional"))
    )
    (net (code "38") (name "T_0") (class "Default")
      (node (ref "R8") (pin "2") (pinfunction "2_2") (pintype "passive"))
      (node (ref "RN1") (pin "12") (pinfunction "12_12") (pintype "bidirectional"))
      (node (ref "U$1") (pin "17/A3") (pinfunction "17/A3/TX4_17/A3") (pintype "bidirectional"))
    )
    (net (code "39") (name "T_1") (class "Default")
      (node (ref "RN1") (pin "10") (pinfunction "10_10") (pintype "bidirectional"))
      (node (ref "T1") (pin "2") (pinfunction "2_2") (pintype "passive"))
      (node (ref "U$1") (pin "15/A1") (pinfunction "15/A1/RX3_15/A1") (pintype "bidirectional"))
    )
    (net (code "40") (name "V_0") (class "Default")
      (node (ref "RN1") (pin "9") (pinfunction "9_9") (pintype "bidirectional"))
      (node (ref "RN2") (pin "8") (pinfunction "8_8") (pintype "bidirectional"))
      (node (ref "U$1") (pin "14/A0") (pinfunction "14/A0/TX3_14/A0") (pintype "bidirectional"))
    )
    (net (code "41") (name "V_1") (class "Default")
      (node (ref "RN1") (pin "11") (pinfunction "11_11") (pintype "bidirectional"))
      (node (ref "RN2") (pin "6") (pinfunction "6_6") (pintype "bidirectional"))
      (node (ref "U$1") (pin "16/A2") (pinfunction "16/A2/RX4_16/A2") (pintype "bidirectional"))
    )
    (net (code "42") (name "unconnected-(J1-Pad4)") (class "Default")
      (node (ref "J1") (pin "4") (pinfunction "4_4") (pintype "passive"))
    )
    (net (code "43") (name "unconnected-(J1-Pad6)") (class "Default")
      (node (ref "J1") (pin "6") (pinfunction "6_6") (pintype "passive"))
    )
    (net (code "44") (name "unconnected-(J1-Pad9)") (class "Default")
      (node (ref "J1") (pin "9") (pinfunction "9_9") (pintype "passive"))
    )
    (net (code "45") (name "unconnected-(J1-Pad12)") (class "Default")
      (node (ref "J1") (pin "12") (pinfunction "12_12") (pintype "passive"))
    )
    (net (code "46") (name "unconnected-(J1-Pad14)") (class "Default")
      (node (ref "J1") (pin "14") (pinfunction "14_14") (pintype "passive"))
    )
    (net (code "47") (name "unconnected-(J1-Pad16)") (class "Default")
      (node (ref "J1") (pin "16") (pinfunction "16_16") (pintype "passive"))
    )
    (net (code "48") (name "unconnected-(J1-Pad17)") (class "Default")
      (node (ref "J1") (pin "17") (pinfunction "17_17") (pintype "passive"))
    )
    (net (code "49") (name "unconnected-(J1-Pad20)") (class "Default")
      (node (ref "J1") (pin "20") (pinfunction "20_20") (pintype "passive"))
    )
    (net (code "50") (name "unconnected-(J1-Pad22)") (class "Default")
      (node (ref "J1") (pin "22") (pinfunction "22_22") (pintype "passive"))
    )
    (net (code "51") (name "unconnected-(J1-Pad23)") (class "Default")
      (node (ref "J1") (pin "23") (pinfunction "23_23") (pintype "passive"))
    )
    (net (code "52") (name "unconnected-(J1-Pad24)") (class "Default")
      (node (ref "J1") (pin "24") (pinfunction "24_24") (pintype "passive"))
    )
    (net (code "53") (name "unconnected-(J1-Pad25)") (class "Default")
      (node (ref "J1") (pin "25") (pinfunction "25_25") (pintype "passive"))
    )
    (net (code "54") (name "unconnected-(J1-Pad27)") (class "Default")
      (node (ref "J1") (pin "27") (pinfunction "27_27") (pintype "passive"))
    )
    (net (code "55") (name "unconnected-(J1-Pad28)") (class "Default")
      (node (ref "J1") (pin "28") (pinfunction "28_28") (pintype "passive"))
    )
    (net (code "56") (name "unconnected-(J1-Pad31)") (class "Default")
      (node (ref "J1") (pin "31") (pinfunction "31_31") (pintype "passive"))
    )
    (net (code "57") (name "unconnected-(J1-Pad32)") (class "Default")
      (node (ref "J1") (pin "32") (pinfunction "32_32") (pintype "passive"))
    )
    (net (code "58") (name "unconnected-(J1-Pad34)") (class "Default")
      (node (ref "J1") (pin "34") (pinfunction "34_34") (pintype "passive"))
    )
    (net (code "59") (name "unconnected-(J1-Pad36)") (class "Default")
      (node (ref "J1") (pin "36") (pinfunction "36_36") (pintype "passive"))
    )
    (net (code "60") (name "unconnected-(J1-Pad37)") (class "Default")
      (node (ref "J1") (pin "37") (pinfunction "37_37") (pintype "passive"))
    )
    (net (code "61") (name "unconnected-(J1-Pad38)") (class "Default")
      (node (ref "J1") (pin "38") (pinfunction "38_38") (pintype "passive"))
    )
    (net (code "62") (name "unconnected-(J1-Pad39)") (class "Default")
      (node (ref "J1") (pin "39") (pinfunction "39_39") (pintype "passive"))
    )
    (net (code "63") (name "unconnected-(U$1-Pad3V3_LN)") (class "Default")
      (node (ref "U$1") (pin "3V3_LN") (pinfunction "3V3_LN_3V3_LN") (pintype "bidirectional"))
    )
    (net (code "64") (name "unconnected-(U$1-PadGND3)") (class "Default")
      (node (ref "U$1") (pin "GND3") (pinfunction "GND3_GND3") (pintype "bidirectional"))
    )
    (net (code "65") (name "unconnected-(U$1-PadON{slash}OFF)") (class "Default")
      (node (ref "U$1") (pin "ON/OFF") (pinfunction "ON/OFF_ON/OFF") (pintype "bidirectional"))
    )
    (net (code "66") (name "unconnected-(U$1-PadPROG)") (class "Default")
      (node (ref "U$1") (pin "PROG") (pinfunction "PROG_PROG") (pintype "bidirectional"))
    )
    (net (code "67") (name "unconnected-(U$1-VBAT-PadVBAT\\)") (class "Default")
      (node (ref "U$1") (pin "VBAT\\") (pinfunction "VBAT_VBAT\\") (pintype "bidirectional"))
    )
    (net (code "68") (name "unconnected-(U$3-Pad3VOUT)") (class "Default")
      (node (ref "U$3") (pin "3VOUT") (pinfunction "3VOUT_3VOUT") (pintype "bidirectional"))
    )
    (net (code "69") (name "unconnected-(U$3-PadADDR)") (class "Default")
      (node (ref "U$3") (pin "ADDR") (pinfunction "ADDR_ADDR") (pintype "bidirectional"))
    )
    (net (code "70") (name "unconnected-(U$3-PadINT)") (class "Default")
      (node (ref "U$3") (pin "INT") (pinfunction "INT_INT") (pintype "bidirectional"))
    )
    (net (code "71") (name "unconnected-(U$3-PadPS0)") (class "Default")
      (node (ref "U$3") (pin "PS0") (pinfunction "PS0_PS0") (pintype "bidirectional"))
    )
    (net (code "72") (name "unconnected-(U$3-PadPS1)") (class "Default")
      (node (ref "U$3") (pin "PS1") (pinfunction "PS1_PS1") (pintype "bidirectional"))
    )
    (net (code "73") (name "unconnected-(U$3-PadRST)") (class "Default")
      (node (ref "U$3") (pin "RST") (pinfunction "RST_RST") (pintype "bidirectional"))
    )
    (net (code "74") (name "unconnected-(U1-~{WP}-Pad3)") (class "Default")
      (node (ref "U1") (pin "3") (pinfunction "~{WP}_3") (pintype "bidirectional"))
    )
    (net (code "75") (name "unconnected-(U2-~{WP}-Pad3)") (class "Default")
      (node (ref "U2") (pin "3") (pinfunction "~{WP}_3") (pintype "bidirectional"))
    )
    (net (code "76") (name "unconnected-(U3-~{WP}-Pad3)") (class "Default")
      (node (ref "U3") (pin "3") (pinfunction "~{WP}_3") (pintype "bidirectional"))
    )
  )
)
